# Power_Rails.net
KiCad netlist of a schematic drawn in Altium Designer
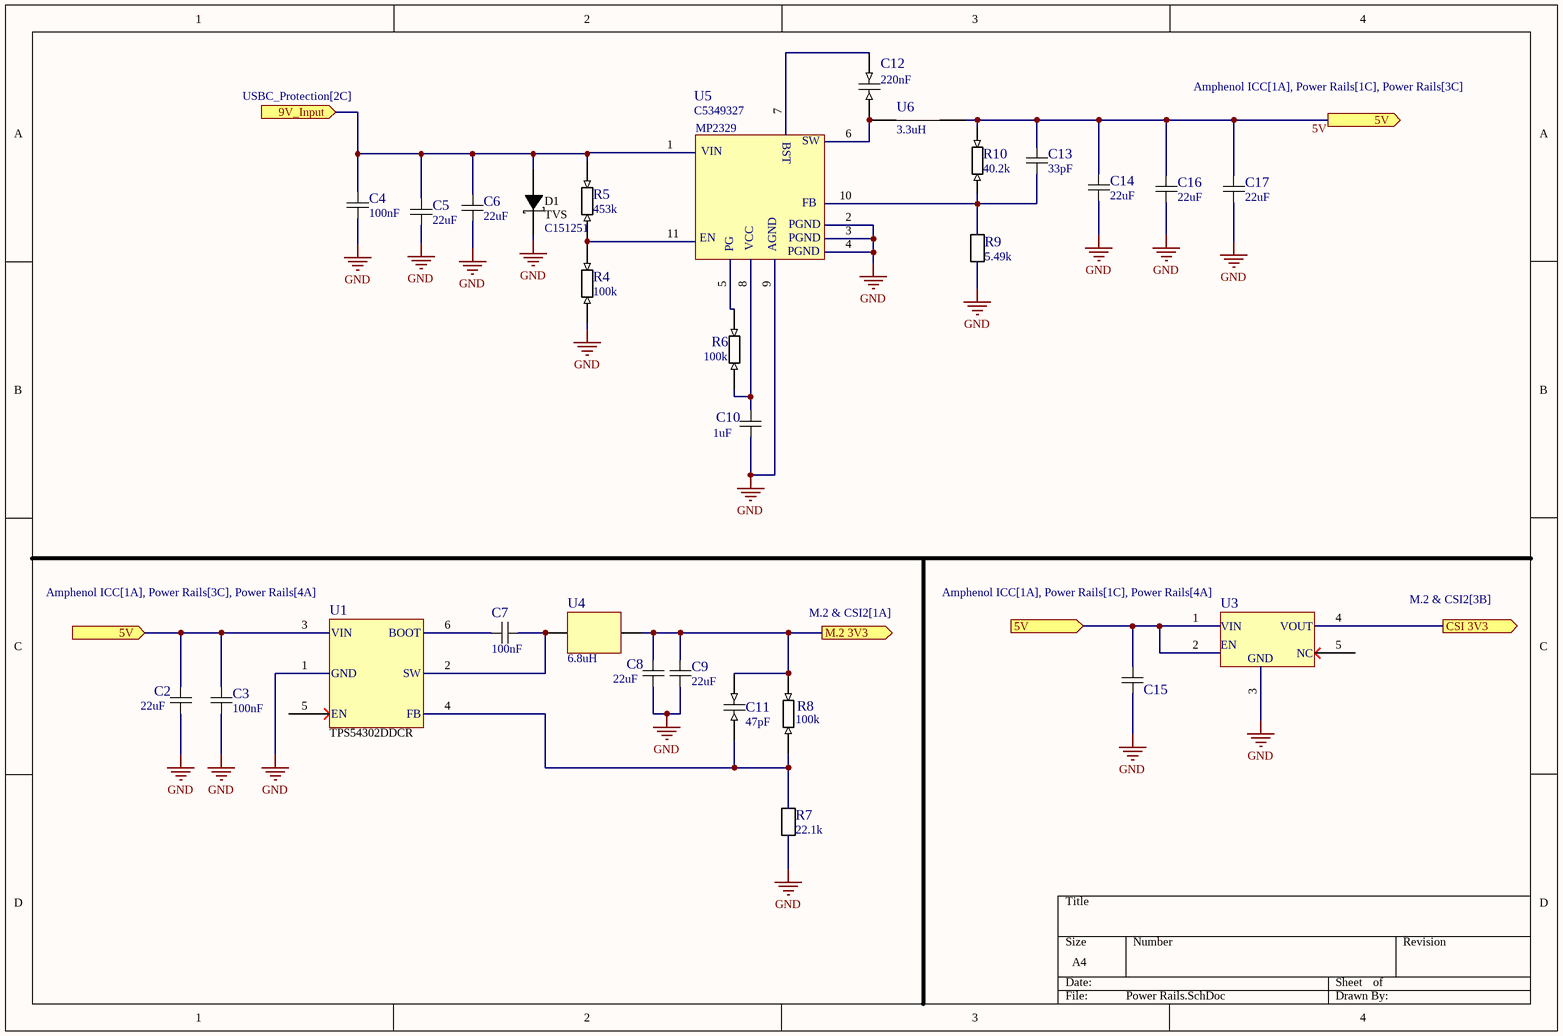
[diagram p0: Power Rails.SchDoc]

(export (version "E")
  (design (tool "Eeschema 10.0.6"))
  (components
    (comp (ref "C2")
      (value "22uF")
      (footprint "C0805")
      (description "22uF ±20% 25V Ceramic Capacitor X5R 0805")
      (fields (field (name "Comment") "CL21A226MAQNNNE") (field (name "SOURCE") "LCSC"))
      (libsource (lib "C45783") (part "CL21A226MAQNNNE"))
    )
    (comp (ref "C3")
      (value "100nF")
      (footprint "C0603")
      (description "100nF ±10% 50V Ceramic Capacitor X7R 0603")
      (fields (field (name "Comment") "CC0603KRX7R9BB104") (field (name "SOURCE") "LCSC"))
      (libsource (lib "C14663") (part "CC0603KRX7R9BB104"))
    )
    (comp (ref "C4")
      (value "100nF")
      (footprint "C0603")
      (description "C0603X7R104K250NT")
      (fields (field (name "SOURCE") "LCSC"))
      (libsource (lib "C466768") (part "C0603X7R104K250NT"))
    )
    (comp (ref "C5")
      (value "22uF")
      (footprint "C0805")
      (description "22uF ±20% 25V Ceramic Capacitor X5R 0805")
      (fields (field (name "Comment") "CL21A226MAQNNNE") (field (name "SOURCE") "LCSC"))
      (libsource (lib "C45783") (part "CL21A226MAQNNNE"))
    )
    (comp (ref "C6")
      (value "22uF")
      (footprint "C0805")
      (description "22uF ±20% 25V Ceramic Capacitor X5R 0805")
      (fields (field (name "Comment") "CL21A226MAQNNNE") (field (name "SOURCE") "LCSC"))
      (libsource (lib "C45783") (part "CL21A226MAQNNNE"))
    )
    (comp (ref "C7")
      (value "100nF")
      (footprint "C0603")
      (description "100nF ±10% 50V Ceramic Capacitor X7R 0603")
      (fields (field (name "Comment") "CC0603KRX7R9BB104") (field (name "SOURCE") "LCSC"))
      (libsource (lib "C14663") (part "CC0603KRX7R9BB104"))
    )
    (comp (ref "C8")
      (value "22uF")
      (footprint "C0805")
      (description "22uF ±20% 25V Ceramic Capacitor X5R 0805")
      (fields (field (name "Comment") "CL21A226MAQNNNE") (field (name "SOURCE") "LCSC"))
      (libsource (lib "C45783") (part "CL21A226MAQNNNE"))
    )
    (comp (ref "C9")
      (value "22uF")
      (footprint "C0805")
      (description "22uF ±20% 25V Ceramic Capacitor X5R 0805")
      (fields (field (name "Comment") "CL21A226MAQNNNE") (field (name "SOURCE") "LCSC"))
      (libsource (lib "C45783") (part "CL21A226MAQNNNE"))
    )
    (comp (ref "C10")
      (value "1uF")
      (footprint "C0603")
      (description "1uF ±10% 50V Ceramic Capacitor X5R 0603")
      (fields (field (name "Comment") "CL10A105KB8NNNC") (field (name "SOURCE") "LCSC"))
      (libsource (lib "C15849") (part "CL10A105KB8NNNC"))
    )
    (comp (ref "C11")
      (value "47pF")
      (footprint "C0603")
      (description "47pF ±5% 50V Ceramic Capacitor C0G 0603")
      (fields (field (name "Comment") "CL10C470JB8NNNC") (field (name "SOURCE") "LCSC"))
      (libsource (lib "C1671") (part "CL10C470JB8NNNC"))
    )
    (comp (ref "C12")
      (value "220nF")
      (footprint "C0603")
      (description "220nF ±10% 25V Ceramic Capacitor X7R 0603")
      (fields (field (name "Comment") "CL10B224KA8NNNC") (field (name "SOURCE") "LCSC"))
      (libsource (lib "C21120") (part "CL10B224KA8NNNC"))
    )
    (comp (ref "C13")
      (value "33pF")
      (footprint "C0603")
      (description "33pF C0G ±1% 50V 0603 Ceramic Capacitors")
      (fields (field (name "Comment") "TCC0603COG330F500CT") (field (name "SOURCE") "LCSC"))
      (libsource (lib "C48543706") (part "TCC0603COG330F500CT"))
    )
    (comp (ref "C14")
      (value "22uF")
      (footprint "C0805")
      (description "22uF ±20% 25V Ceramic Capacitor X5R 0805")
      (fields (field (name "Comment") "CL21A226MAQNNNE") (field (name "SOURCE") "LCSC"))
      (libsource (lib "C45783") (part "CL21A226MAQNNNE"))
    )
    (comp (ref "C15")
      (value "CL10A105KB8NNNC")
      (footprint "C0603")
      (description "1uF ±10% 50V Ceramic Capacitor X5R 0603")
      (fields (field (name "SOURCE") "LCSC"))
      (libsource (lib "C15849") (part "CL10A105KB8NNNC"))
    )
    (comp (ref "C16")
      (value "22uF")
      (footprint "C0805")
      (description "22uF ±20% 25V Ceramic Capacitor X5R 0805")
      (fields (field (name "Comment") "CL21A226MAQNNNE") (field (name "SOURCE") "LCSC"))
      (libsource (lib "C45783") (part "CL21A226MAQNNNE"))
    )
    (comp (ref "C17")
      (value "22uF")
      (footprint "C0805")
      (description "22uF ±20% 25V Ceramic Capacitor X5R 0805")
      (fields (field (name "Comment") "CL21A226MAQNNNE") (field (name "SOURCE") "LCSC"))
      (libsource (lib "C45783") (part "CL21A226MAQNNNE"))
    )
    (comp (ref "D1")
      (value "TVS")
      (footprint "SMB_L4.6-W3.6-LS5.3-RD")
      (description "21.5VC Clamp 28A@10/1000us Ipp TVS DIODE DO-214AA")
      (fields (field (name "NAME") "C151251") (field (name "SOURCE") "LCSC"))
      (libsource (lib "C151251") (part "SMBJ12A_C151251"))
    )
    (comp (ref "R4")
      (value "100k")
      (footprint "R0603")
      (description "100kÎ© Â±1% 100mW 0603 Thick Film Resistor")
      (fields (field (name "Comment") "0603WAF1003T5E") (field (name "SOURCE") "LCSC"))
      (libsource (lib "C25803") (part "0603WAF1003T5E"))
    )
    (comp (ref "R5")
      (value "453k")
      (footprint "R0603")
      (description "453kÎ© Â±1% 100mW 0603 Thick Film Resistor")
      (fields (field (name "Comment") "0603WAF4533T5E") (field (name "SOURCE") "LCSC"))
      (libsource (lib "C25818") (part "0603WAF4533T5E"))
    )
    (comp (ref "R6")
      (value "100k")
      (footprint "R0603")
      (description "100kÎ© Â±1% 100mW 0603 Thick Film Resistor")
      (fields (field (name "Comment") "0603WAF1003T5E") (field (name "SOURCE") "LCSC"))
      (libsource (lib "C25803") (part "0603WAF1003T5E"))
    )
    (comp (ref "R7")
      (value "22.1k")
      (footprint "R0603")
      (description "22.1kÎ© 100mW 75V Thin Film Resistor Â±25ppm/â„ƒ Â±0.1% 0603 Chip Resistor - Surface Mount RoHS")
      (fields (field (name "Comment") "RT0603BRD0722K1L") (field (name "SOURCE") "LCSC"))
      (libsource (lib "C723484") (part "RT0603BRD0722K1L"))
    )
    (comp (ref "R8")
      (value "100k")
      (footprint "R0603")
      (description "100kÎ© Â±1% 100mW 0603 Thick Film Resistor")
      (fields (field (name "Comment") "0603WAF1003T5E") (field (name "SOURCE") "LCSC"))
      (libsource (lib "C25803") (part "0603WAF1003T5E"))
    )
    (comp (ref "R9")
      (value "5.49k")
      (footprint "R0603")
      (description "5.49kÎ© 100mW 75V Thick Film Resistor Â±100ppm/â„ƒ Â±1% 0603 Chip Resistor - Surface Mount")
      (fields (field (name "Comment") "FRQ0603F5491TS") (field (name "SOURCE") "LCSC"))
      (libsource (lib "C54102278") (part "FRQ0603F5491TS"))
    )
    (comp (ref "R10")
      (value "40.2k")
      (footprint "R0603")
      (description "40.2kÎ© Â±1% 100mW 0603 Thick Film Resistor")
      (fields (field (name "Comment") "0603WAF4022T5E") (field (name "SOURCE") "LCSC"))
      (libsource (lib "C12447") (part "0603WAF4022T5E"))
    )
    (comp (ref "U1")
      (value "TPS54302DDCR")
      (footprint "SOT-23-6_L2.9-W1.6-P0.95-LS2.8-BL")
      (description "Buck Switching Regulator IC Adjustable 1 Output 3A TSOT-23-6")
      (fields (field (name "SOURCE") "LCSC"))
      (libsource (lib "C311983") (part "TPS54302DDCR_C311983"))
    )
    (comp (ref "U3")
      (value "AP2112K-3.3TRG1")
      (footprint "SOT-25-5_L2.9-W1.6-P0.95-LS2.8-BL")
      (description "3.3V Positive Fixed SOT-25-5 Voltage Regulators - Linear, Low Drop Out (LDO) Regulators RoHS")
      (fields (field (name "SOURCE") "LCSC"))
      (libsource (lib "C51118") (part "AP2112K-3.3TRG1"))
    )
    (comp (ref "U4")
      (value "6.8uH")
      (footprint "IND-SMD_L5.7-W5.2")
      (description "3.5A 6.8uH Â±20% 5A 70mÎ© Molded inductor SMD,5.7x5.2mm Fixed Inductors")
      (fields (field (name "Comment") "CXP0530-6R8M-AG(6.8uh)") (field (name "SOURCE") "LCSC"))
      (libsource (lib "C7461350") (part "CXP0530-6R8M-AG_6.8UH"))
    )
    (comp (ref "U5")
      (value "MP2329GG-Z")
      (footprint "QFN-11_L2.0-W2.0-P0.50_MP2384CGG-Z")
      (fields (field (name "NAME") "C5349327") (field (name "SOURCE") "LCSC"))
      (libsource (lib "C5349327") (part "MP2329GG-Z"))
    )
    (comp (ref "U6")
      (value "3.3uH")
      (footprint "IND-SMD_L13.8-W12.8")
      (description "20A 3.3uH ±20% 32A Molded inductor SMD,13.8x12.8mm Fixed Inductors")
      (fields (field (name "Comment") "CYA1250-3.3UH") (field (name "SOURCE") "LCSC"))
      (libsource (lib "C19268654") (part "CYA1250-3.3UH"))
    )
  )
  (nets
    (net (code "1") (name "/5V") (class "Default")
      (node (ref "C13") (pin "2") (pinfunction "2_2") (pintype "passive"))
      (node (ref "C14") (pin "1") (pinfunction "1_1") (pintype "passive"))
      (node (ref "C15") (pin "2") (pinfunction "2_2") (pintype "passive"))
      (node (ref "C16") (pin "1") (pinfunction "1_1") (pintype "passive"))
      (node (ref "C17") (pin "1") (pinfunction "1_1") (pintype "passive"))
      (node (ref "C2") (pin "1") (pinfunction "1_1") (pintype "passive"))
      (node (ref "C3") (pin "2") (pinfunction "2_2") (pintype "passive"))
      (node (ref "R10") (pin "2") (pinfunction "2_2") (pintype "input"))
      (node (ref "U1") (pin "3") (pinfunction "VIN_3") (pintype "passive"))
      (node (ref "U3") (pin "1") (pinfunction "VIN_1") (pintype "passive"))
      (node (ref "U3") (pin "2") (pinfunction "EN_2") (pintype "passive"))
      (node (ref "U6") (pin "2") (pinfunction "2_2") (pintype "passive"))
    )
    (net (code "2") (name "/9V_Input") (class "Default")
      (node (ref "C4") (pin "2") (pinfunction "2_2") (pintype "passive"))
      (node (ref "C5") (pin "2") (pinfunction "2_2") (pintype "passive"))
      (node (ref "C6") (pin "2") (pinfunction "2_2") (pintype "passive"))
      (node (ref "D1") (pin "2") (pinfunction "A_2") (pintype "passive"))
      (node (ref "R5") (pin "2") (pinfunction "2_2") (pintype "input"))
      (node (ref "U5") (pin "1") (pinfunction "1_1") (pintype "passive"))
    )
    (net (code "3") (name "/CSI 3V3") (class "Default")
      (node (ref "U3") (pin "4") (pinfunction "4_4") (pintype "passive"))
    )
    (net (code "4") (name "/M.2 3V3") (class "Default")
      (node (ref "C11") (pin "2") (pinfunction "2_2") (pintype "input"))
      (node (ref "C8") (pin "1") (pinfunction "1_1") (pintype "passive"))
      (node (ref "C9") (pin "1") (pinfunction "1_1") (pintype "passive"))
      (node (ref "R8") (pin "2") (pinfunction "2_2") (pintype "input"))
      (node (ref "U4") (pin "2") (pinfunction "2_2") (pintype "passive"))
    )
    (net (code "5") (name "GND") (class "Default")
      (node (ref "C10") (pin "1") (pinfunction "1_1") (pintype "passive"))
      (node (ref "C14") (pin "2") (pinfunction "2_2") (pintype "passive"))
      (node (ref "C15") (pin "1") (pinfunction "1_1") (pintype "passive"))
      (node (ref "C16") (pin "2") (pinfunction "2_2") (pintype "passive"))
      (node (ref "C17") (pin "2") (pinfunction "2_2") (pintype "passive"))
      (node (ref "C2") (pin "2") (pinfunction "2_2") (pintype "passive"))
      (node (ref "C3") (pin "1") (pinfunction "1_1") (pintype "passive"))
      (node (ref "C4") (pin "1") (pinfunction "1_1") (pintype "passive"))
      (node (ref "C5") (pin "1") (pinfunction "1_1") (pintype "passive"))
      (node (ref "C6") (pin "1") (pinfunction "1_1") (pintype "passive"))
      (node (ref "C8") (pin "2") (pinfunction "2_2") (pintype "passive"))
      (node (ref "C9") (pin "2") (pinfunction "2_2") (pintype "passive"))
      (node (ref "D1") (pin "1") (pinfunction "K_1") (pintype "passive"))
      (node (ref "R4") (pin "1") (pinfunction "1_1") (pintype "input"))
      (node (ref "R7") (pin "1") (pinfunction "1_1") (pintype "passive"))
      (node (ref "R9") (pin "1") (pinfunction "1_1") (pintype "passive"))
      (node (ref "U1") (pin "1") (pinfunction "GND_1") (pintype "passive"))
      (node (ref "U3") (pin "3") (pinfunction "3_3") (pintype "passive"))
      (node (ref "U5") (pin "2") (pinfunction "2_2") (pintype "passive"))
      (node (ref "U5") (pin "3") (pinfunction "3_3") (pintype "passive"))
      (node (ref "U5") (pin "4") (pinfunction "4_4") (pintype "passive"))
      (node (ref "U5") (pin "9") (pinfunction "9_9") (pintype "passive"))
    )
    (net (code "6") (name "Net-(C10-Pad2)") (class "Default")
      (node (ref "C10") (pin "2") (pinfunction "2_2") (pintype "passive"))
      (node (ref "R6") (pin "1") (pinfunction "1_1") (pintype "input"))
      (node (ref "U5") (pin "8") (pinfunction "8_8") (pintype "passive"))
    )
    (net (code "7") (name "Net-(C12-Pad1)") (class "Default")
      (node (ref "C12") (pin "1") (pinfunction "1_1") (pintype "input"))
      (node (ref "U5") (pin "6") (pinfunction "6_6") (pintype "passive"))
      (node (ref "U6") (pin "1") (pinfunction "1_1") (pintype "passive"))
    )
    (net (code "8") (name "Net-(C12-Pad2)") (class "Default")
      (node (ref "C12") (pin "2") (pinfunction "2_2") (pintype "input"))
      (node (ref "U5") (pin "7") (pinfunction "7_7") (pintype "passive"))
    )
    (net (code "9") (name "Net-(C13-Pad1)") (class "Default")
      (node (ref "C13") (pin "1") (pinfunction "1_1") (pintype "passive"))
      (node (ref "R10") (pin "1") (pinfunction "1_1") (pintype "input"))
      (node (ref "R9") (pin "2") (pinfunction "2_2") (pintype "passive"))
      (node (ref "U5") (pin "10") (pinfunction "10_10") (pintype "passive"))
    )
    (net (code "10") (name "Net-(R4-Pad2)") (class "Default")
      (node (ref "R4") (pin "2") (pinfunction "2_2") (pintype "input"))
      (node (ref "R5") (pin "1") (pinfunction "1_1") (pintype "input"))
      (node (ref "U5") (pin "11") (pinfunction "11_11") (pintype "passive"))
    )
    (net (code "11") (name "Net-(R6-Pad2)") (class "Default")
      (node (ref "R6") (pin "2") (pinfunction "2_2") (pintype "input"))
      (node (ref "U5") (pin "5") (pinfunction "5_5") (pintype "passive"))
    )
    (net (code "12") (name "Net-(U1-BOOT)") (class "Default")
      (node (ref "C7") (pin "2") (pinfunction "2_2") (pintype "passive"))
      (node (ref "U1") (pin "6") (pinfunction "BOOT_6") (pintype "passive"))
    )
    (net (code "13") (name "Net-(U1-FB)") (class "Default")
      (node (ref "C11") (pin "1") (pinfunction "1_1") (pintype "input"))
      (node (ref "R7") (pin "2") (pinfunction "2_2") (pintype "passive"))
      (node (ref "R8") (pin "1") (pinfunction "1_1") (pintype "input"))
      (node (ref "U1") (pin "4") (pinfunction "FB_4") (pintype "passive"))
    )
    (net (code "14") (name "Net-(U1-SW)") (class "Default")
      (node (ref "C7") (pin "1") (pinfunction "1_1") (pintype "passive"))
      (node (ref "U1") (pin "2") (pinfunction "SW_2") (pintype "passive"))
      (node (ref "U4") (pin "1") (pinfunction "1_1") (pintype "passive"))
    )
    (net (code "15") (name "unconnected-(U1-EN-Pad5)") (class "Default")
      (node (ref "U1") (pin "5") (pinfunction "EN_5") (pintype "passive+no_connect"))
    )
    (net (code "16") (name "unconnected-(U3-Pad5)") (class "Default")
      (node (ref "U3") (pin "5") (pinfunction "5_5") (pintype "passive+no_connect"))
    )
  )
)
